# Sheet1_MCU.net
KiCad netlist of a schematic drawn in Altium Designer
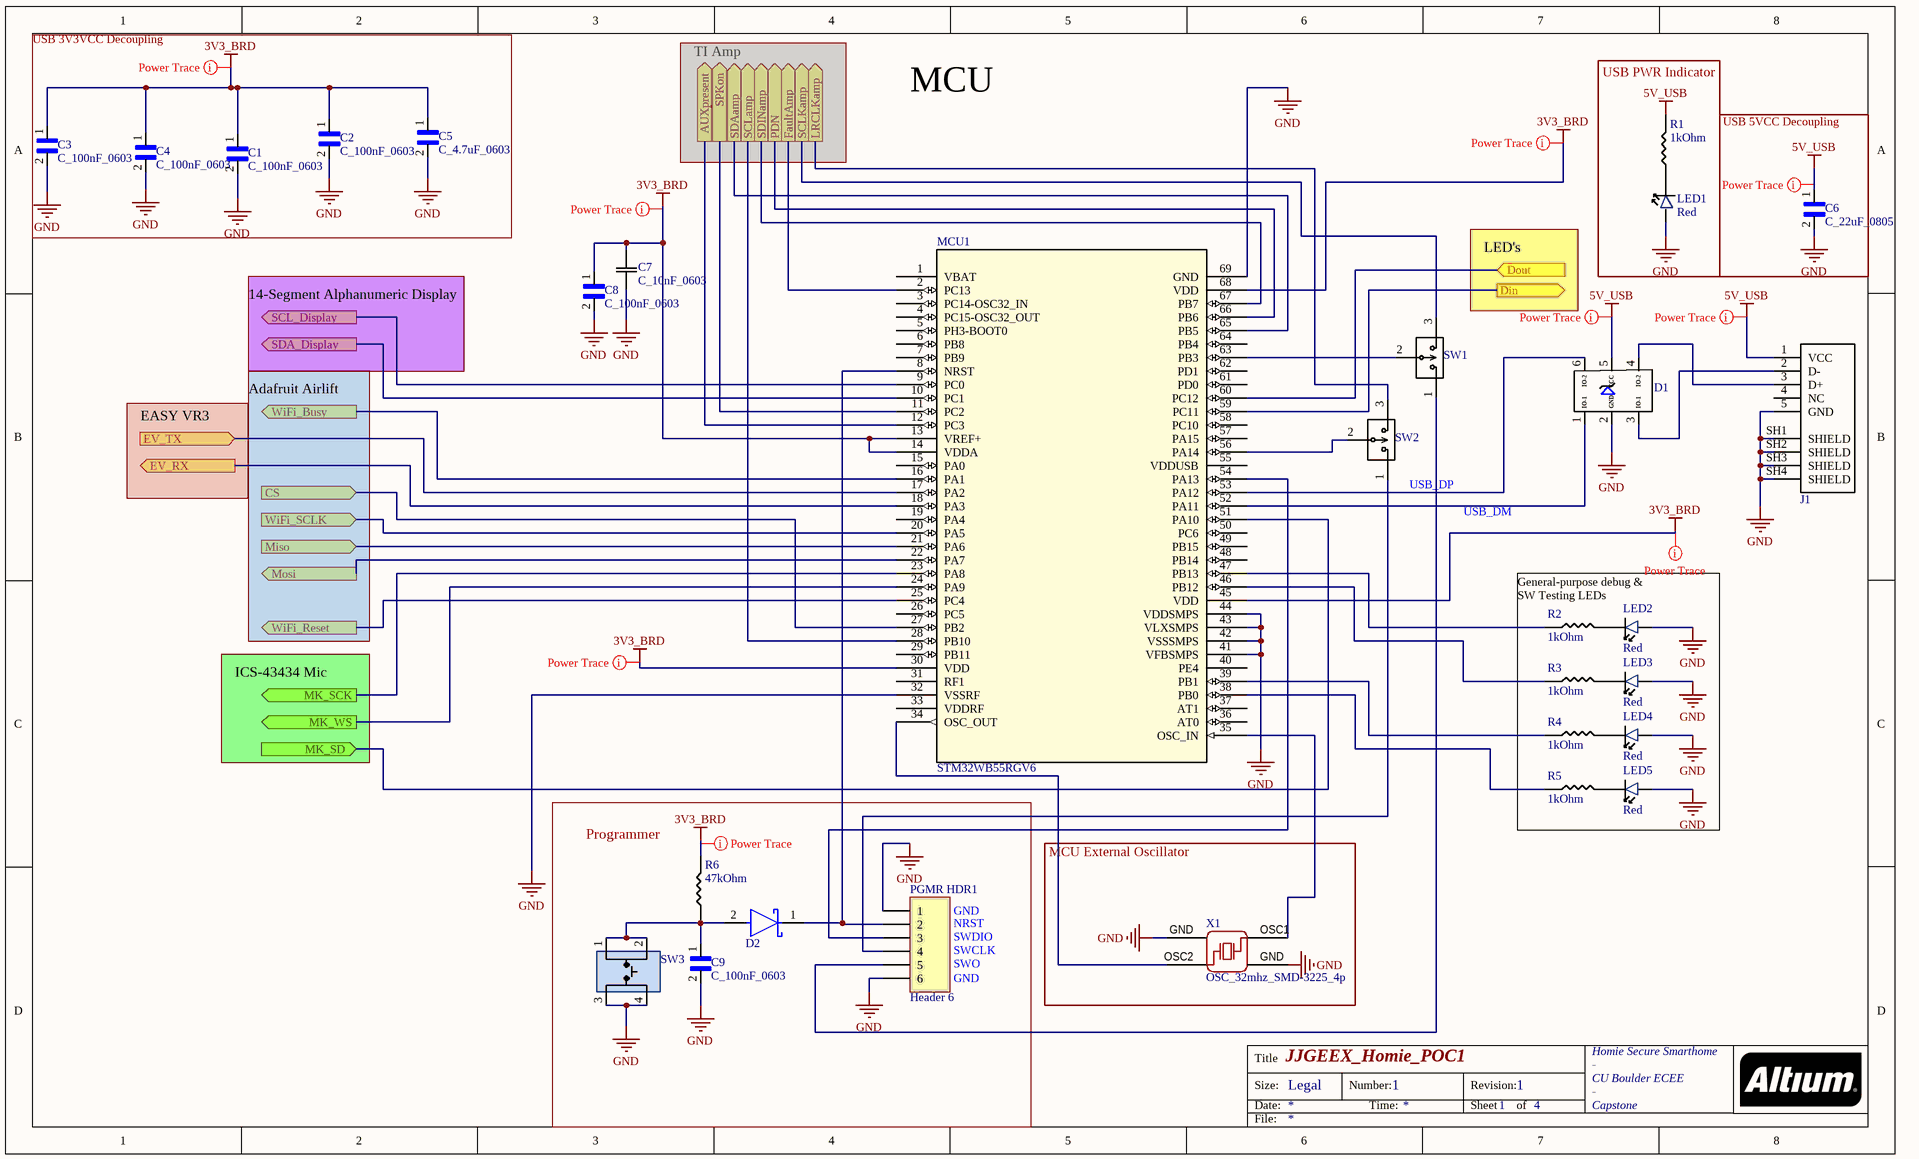
[diagram p0: Sheet1_MCU.SchDoc]

(export (version "E")
  (design (tool "Eeschema 10.0.6"))
  (components
    (comp (ref "C1")
      (value "C_100nF_0603")
      (footprint "CAPC1608X90")
      (description "0.1礔/100nF  卤10% 50V Ceramic Capacitor X7R 0603 _1608 Metric_")
      (fields (field (name "DIGI-KEY_PART_NUMBER") "311-1344-1-ND") (field (name "MP") "CC0603KRX7R9BB104"))
      (libsource (lib "Homie_IntegratedLibraryV2") (part "C_100nF_0603"))
    )
    (comp (ref "C2")
      (value "C_100nF_0603")
      (footprint "CAPC1608X90")
      (description "0.1礔/100nF  卤10% 50V Ceramic Capacitor X7R 0603 _1608 Metric_")
      (fields (field (name "DIGI-KEY_PART_NUMBER") "311-1344-1-ND") (field (name "MP") "CC0603KRX7R9BB104"))
      (libsource (lib "Homie_IntegratedLibraryV2") (part "C_100nF_0603"))
    )
    (comp (ref "C3")
      (value "C_100nF_0603")
      (footprint "CAPC1608X90")
      (description "0.1礔/100nF  卤10% 50V Ceramic Capacitor X7R 0603 _1608 Metric_")
      (fields (field (name "DIGI-KEY_PART_NUMBER") "311-1344-1-ND") (field (name "MP") "CC0603KRX7R9BB104"))
      (libsource (lib "Homie_IntegratedLibraryV2") (part "C_100nF_0603"))
    )
    (comp (ref "C4")
      (value "C_100nF_0603")
      (footprint "CAPC1608X90")
      (description "0.1礔/100nF  卤10% 50V Ceramic Capacitor X7R 0603 _1608 Metric_")
      (fields (field (name "DIGI-KEY_PART_NUMBER") "311-1344-1-ND") (field (name "MP") "CC0603KRX7R9BB104"))
      (libsource (lib "Homie_IntegratedLibraryV2") (part "C_100nF_0603"))
    )
    (comp (ref "C5")
      (value "C_4.7uF_0603")
      (footprint "CAPC1608X90N")
      (description "4.7µF ±10% 16V Ceramic Capacitor X5R 0603 (1608 Metric)")
      (fields (field (name "MF") "Samsung Electro-Mechanics") (field (name "MP") "CL10A475KO8NNNC"))
      (libsource (lib "Homie_IntegratedLibraryV2") (part "C_4.7uF_0603"))
    )
    (comp (ref "C6")
      (value "C_22uF_0805")
      (footprint "CAPC2012X140N")
      (description "22µF 0805 ±20% 25V Ceramic Capacitor X5R 0805 (2012 Metric)")
      (fields (field (name "MF") "Samsung") (field (name "DIGI-KEY_PART_NUMBER") "1276-2908-1-ND"))
      (libsource (lib "Homie_IntegratedLibraryV2") (part "C_22uF_0805"))
    )
    (comp (ref "C7")
      (value "C_10nF_0603")
      (footprint "CAP_0603_S_WAL")
      (description "10nf 0603 cap")
      (fields
        (field (name "MANUFACTURER_PART_NUMBER") "0603B103J100CT")
        (field (name "COPYRIGHT") "Copyright (C) 2018 Accelerated Designs. All rights reserved")
      )
      (libsource (lib "Homie_IntegratedLibraryV2") (part "C_10nF_0603"))
    )
    (comp (ref "C8")
      (value "C_100nF_0603")
      (footprint "CAPC1608X90")
      (description "0.1礔/100nF  卤10% 50V Ceramic Capacitor X7R 0603 _1608 Metric_")
      (fields (field (name "DIGI-KEY_PART_NUMBER") "311-1344-1-ND") (field (name "MP") "CC0603KRX7R9BB104"))
      (libsource (lib "Homie_IntegratedLibraryV2") (part "C_100nF_0603"))
    )
    (comp (ref "C9")
      (value "C_100nF_0603")
      (footprint "CAPC1608X90")
      (description "0.1礔/100nF  卤10% 50V Ceramic Capacitor X7R 0603 _1608 Metric_")
      (fields (field (name "DIGI-KEY_PART_NUMBER") "311-1344-1-ND") (field (name "MP") "CC0603KRX7R9BB104"))
      (libsource (lib "Homie_IntegratedLibraryV2") (part "C_100nF_0603"))
    )
    (comp (ref "D1")
      (value "IP4234CZ6,125")
      (footprint "TVS")
      (description "Clamp Ipp Tvs Diode Surface Mount 6-TSOP")
      (fields (field (name "DIGIKEY PART") "1727-4717-1-ND") (field (name "LCSC PART#") "C455086"))
      (libsource (lib "ECEN5730Lib_2020_09_AR") (part "D_TVS_Diode"))
    )
    (comp (ref "D2")
      (value "BAT54KFILM")
      (footprint "STMicroelectronics_SOD-523_MFG")
      (description "BAT54 Diode")
      (fields (field (name "MANUFACTURER") "STMicroelectronics"))
      (libsource (lib "Homie_IntegratedLibraryV2") (part "BAT54KFILM"))
    )
    (comp (ref "J1")
      (value "XM7D-0512")
      (footprint "USB_2")
      (description "USB - mini B USB 2.0 Receptacle Connector 5 Position Through Hole, Right Angle")
      (fields (field (name "DIGIKEY PART") "OR1205-ND"))
      (libsource (lib "ECEN5730Lib_2020_09_AR") (part "J_USB_2_B_Mini"))
    )
    (comp (ref "LED1")
      (value "Red")
      (footprint "LED0603-R-RD")
      (description "LIGHT EMITTING DIODES (LED) RED 520~625NM 90~100MCD@20MA TOP VIEW 0603 ROHS")
      (fields (field (name "MFR") "Hubei KENTO Elec") (field (name "Comment") "KT-0603R"))
      (libsource (lib "Homie_IntegratedLibraryV2") (part "LED_RED_0603"))
    )
    (comp (ref "LED2")
      (value "Red")
      (footprint "LED0603-R-RD")
      (description "LIGHT EMITTING DIODES (LED) RED 520~625NM 90~100MCD@20MA TOP VIEW 0603 ROHS")
      (fields (field (name "MFR") "Hubei KENTO Elec") (field (name "Comment") "KT-0603R"))
      (libsource (lib "Homie_IntegratedLibraryV2") (part "LED_RED_0603"))
    )
    (comp (ref "LED3")
      (value "Red")
      (footprint "LED0603-R-RD")
      (description "LIGHT EMITTING DIODES (LED) RED 520~625NM 90~100MCD@20MA TOP VIEW 0603 ROHS")
      (fields (field (name "MFR") "Hubei KENTO Elec") (field (name "Comment") "KT-0603R"))
      (libsource (lib "Homie_IntegratedLibraryV2") (part "LED_RED_0603"))
    )
    (comp (ref "LED4")
      (value "Red")
      (footprint "LED0603-R-RD")
      (description "LIGHT EMITTING DIODES (LED) RED 520~625NM 90~100MCD@20MA TOP VIEW 0603 ROHS")
      (fields (field (name "MFR") "Hubei KENTO Elec") (field (name "Comment") "KT-0603R"))
      (libsource (lib "Homie_IntegratedLibraryV2") (part "LED_RED_0603"))
    )
    (comp (ref "LED5")
      (value "Red")
      (footprint "LED0603-R-RD")
      (description "LIGHT EMITTING DIODES (LED) RED 520~625NM 90~100MCD@20MA TOP VIEW 0603 ROHS")
      (fields (field (name "MFR") "Hubei KENTO Elec") (field (name "Comment") "KT-0603R"))
      (libsource (lib "Homie_IntegratedLibraryV2") (part "LED_RED_0603"))
    )
    (comp (ref "MCU1")
      (value "STM32WB55RGV6")
      (footprint "VFQFPN68_8X8_STM")
      (description "STM32 Microcontroller")
      (fields (field (name "COPYRIGHT") "Copyright (C) 2018 Accelerated Designs. All rights reserved"))
      (libsource (lib "Homie_IntegratedLibraryV2") (part "STM32WB55RGV6"))
    )
    (comp (ref "PGMR HDR1")
      (value "Header 6")
      (footprint "HDR1X6")
      (description "Header, 6-Pin")
      (fields (field (name "PUBLISHER") "Altium Limited"))
      (libsource (lib "Miscellaneous Connectors") (part "Header 6"))
    )
    (comp (ref "R1")
      (value "1kOhm")
      (footprint "R0603")
      (description "1kOhm +-1%  0603")
      (fields (field (name "MFR") "Uniroyal") (field (name "Comment") "1 kOhm"))
      (libsource (lib "Homie_IntegratedLibraryV2") (part "R_1kOhm_0603"))
    )
    (comp (ref "R2")
      (value "1kOhm")
      (footprint "R0603")
      (description "1kOhm +-1%  0603")
      (fields (field (name "MFR") "Uniroyal") (field (name "Comment") "1 kOhm"))
      (libsource (lib "Homie_IntegratedLibraryV2") (part "R_1kOhm_0603"))
    )
    (comp (ref "R3")
      (value "1kOhm")
      (footprint "R0603")
      (description "1kOhm +-1%  0603")
      (fields (field (name "MFR") "Uniroyal") (field (name "Comment") "1 kOhm"))
      (libsource (lib "Homie_IntegratedLibraryV2") (part "R_1kOhm_0603"))
    )
    (comp (ref "R4")
      (value "1kOhm")
      (footprint "R0603")
      (description "1kOhm +-1%  0603")
      (fields (field (name "MFR") "Uniroyal") (field (name "Comment") "1 kOhm"))
      (libsource (lib "Homie_IntegratedLibraryV2") (part "R_1kOhm_0603"))
    )
    (comp (ref "R5")
      (value "1kOhm")
      (footprint "R0603")
      (description "1kOhm +-1%  0603")
      (fields (field (name "MFR") "Uniroyal") (field (name "Comment") "1 kOhm"))
      (libsource (lib "Homie_IntegratedLibraryV2") (part "R_1kOhm_0603"))
    )
    (comp (ref "R6")
      (value "47kOhm")
      (footprint "R0603")
      (description "47kOhm +-1%")
      (fields (field (name "MFR") "Uniroyal") (field (name "Comment") "47 kOhm"))
      (libsource (lib "Homie_IntegratedLibraryV2") (part "R_47kOhm_0603"))
    )
    (comp (ref "SW1")
      (value "PREC003SAAN-RC")
      (footprint "3_PIN_100mil")
      (description "Connector Header Through Hole 3 position 0.100\" (2.54mm)")
      (fields (field (name "DIGIKEY PART") "S1012EC-03-ND"))
      (libsource (lib "ECEN5730Lib_2020_09_AR") (part "SW_3Pin_100mil_Switch"))
    )
    (comp (ref "SW2")
      (value "PREC003SAAN-RC")
      (footprint "3_PIN_100mil")
      (description "Connector Header Through Hole 3 position 0.100\" (2.54mm)")
      (fields (field (name "DIGIKEY PART") "S1012EC-03-ND"))
      (libsource (lib "ECEN5730Lib_2020_09_AR") (part "SW_3Pin_100mil_Switch"))
    )
    (comp (ref "SW3")
      (value "TL3305AF160QG")
      (footprint "Switch_JLC")
      (description "Tactile Switch SPST-NO Top Actuated Surface Mount")
      (fields (field (name "DIGIKEY PART") "EG5350CT-ND") (field (name "MFR PART #") "UK-B0228-G5-160-JZ"))
      (libsource (lib "ECEN5730Lib_2020_09_AR") (part "SW_Push_Button_JLC"))
    )
    (comp (ref "X1")
      (value "OSC_32mhz_SMD-3225_4p")
      (footprint "OSC-SMD_4P-L3.2-W2.5-BL")
      (description "SMD CRYSTAL RESONATORS 32MHZ ±10PPM SMD-3225_4P ROHS")
      (fields (field (name "MFR") "Seiko Epson"))
      (libsource (lib "Homie_IntegratedLibraryV2") (part "OSC_32mhz_SMD-3225_4p"))
    )
  )
  (nets
    (net (code "1") (name "/AUXpresent") (class "Default")
      (node (ref "MCU1") (pin "12") (pinfunction "PC3_12") (pintype "bidirectional"))
    )
    (net (code "2") (name "/CS") (class "Default")
      (node (ref "MCU1") (pin "27") (pinfunction "PB2_27") (pintype "bidirectional"))
    )
    (net (code "3") (name "/Din") (class "Default")
      (node (ref "MCU1") (pin "59") (pinfunction "PC11_59") (pintype "bidirectional"))
    )
    (net (code "4") (name "/Dout") (class "Default")
      (node (ref "MCU1") (pin "60") (pinfunction "PC12_60") (pintype "bidirectional"))
    )
    (net (code "5") (name "/EV_RX") (class "Default")
      (node (ref "MCU1") (pin "18") (pinfunction "PA3_18") (pintype "bidirectional"))
    )
    (net (code "6") (name "/EV_TX") (class "Default")
      (node (ref "MCU1") (pin "17") (pinfunction "PA2_17") (pintype "bidirectional"))
    )
    (net (code "7") (name "/FaultAmp") (class "Default")
      (node (ref "MCU1") (pin "2") (pinfunction "PC13_2") (pintype "bidirectional"))
    )
    (net (code "8") (name "/LRCLKamp") (class "Default")
      (node (ref "SW2") (pin "3") (pinfunction "3_3") (pintype "passive"))
    )
    (net (code "9") (name "/MK_SCK") (class "Default")
      (node (ref "MCU1") (pin "23") (pinfunction "PA8_23") (pintype "bidirectional"))
    )
    (net (code "10") (name "/MK_SD") (class "Default")
      (node (ref "MCU1") (pin "51") (pinfunction "PA10_51") (pintype "bidirectional"))
    )
    (net (code "11") (name "/MK_WS") (class "Default")
      (node (ref "MCU1") (pin "24") (pinfunction "PA9_24") (pintype "bidirectional"))
    )
    (net (code "12") (name "/Miso") (class "Default")
      (node (ref "MCU1") (pin "21") (pinfunction "PA6_21") (pintype "bidirectional"))
    )
    (net (code "13") (name "/Mosi") (class "Default")
      (node (ref "MCU1") (pin "22") (pinfunction "PA7_22") (pintype "bidirectional"))
    )
    (net (code "14") (name "/PDN") (class "Default")
      (node (ref "MCU1") (pin "66") (pinfunction "PB6_66") (pintype "bidirectional"))
    )
    (net (code "15") (name "/SCLKamp") (class "Default")
      (node (ref "SW1") (pin "3") (pinfunction "3_3") (pintype "passive"))
    )
    (net (code "16") (name "/SCL_Display") (class "Default")
      (node (ref "MCU1") (pin "9") (pinfunction "PC0_9") (pintype "bidirectional"))
    )
    (net (code "17") (name "/SCLamp") (class "Default")
      (node (ref "MCU1") (pin "28") (pinfunction "PB10_28") (pintype "bidirectional"))
    )
    (net (code "18") (name "/SDA_Display") (class "Default")
      (node (ref "MCU1") (pin "10") (pinfunction "PC1_10") (pintype "bidirectional"))
    )
    (net (code "19") (name "/SDAamp") (class "Default")
      (node (ref "MCU1") (pin "65") (pinfunction "PB5_65") (pintype "bidirectional"))
    )
    (net (code "20") (name "/SDINamp") (class "Default")
      (node (ref "MCU1") (pin "67") (pinfunction "PB7_67") (pintype "bidirectional"))
    )
    (net (code "21") (name "/SPKon") (class "Default")
      (node (ref "MCU1") (pin "11") (pinfunction "PC2_11") (pintype "bidirectional"))
    )
    (net (code "22") (name "/WiFi_Busy") (class "Default")
      (node (ref "MCU1") (pin "16") (pinfunction "PA1_16") (pintype "bidirectional"))
    )
    (net (code "23") (name "/WiFi_Reset") (class "Default")
      (node (ref "MCU1") (pin "25") (pinfunction "PC4_25") (pintype "bidirectional"))
    )
    (net (code "24") (name "/WiFi_SCLK") (class "Default")
      (node (ref "MCU1") (pin "20") (pinfunction "PA5_20") (pintype "bidirectional"))
    )
    (net (code "25") (name "3V3_BRD") (class "Default")
      (node (ref "C1") (pin "1") (pinfunction "1_1") (pintype "passive"))
      (node (ref "C2") (pin "1") (pinfunction "1_1") (pintype "passive"))
      (node (ref "C3") (pin "1") (pinfunction "1_1") (pintype "passive"))
      (node (ref "C4") (pin "1") (pinfunction "1_1") (pintype "passive"))
      (node (ref "C5") (pin "1") (pinfunction "1_1") (pintype "passive"))
      (node (ref "C7") (pin "2") (pinfunction "2_2") (pintype "passive"))
      (node (ref "C8") (pin "1") (pinfunction "1_1") (pintype "passive"))
      (node (ref "MCU1") (pin "13") (pinfunction "VREF+_13") (pintype "power_in"))
      (node (ref "MCU1") (pin "14") (pinfunction "VDDA_14") (pintype "power_in"))
      (node (ref "MCU1") (pin "30") (pinfunction "VDD_30") (pintype "power_in"))
      (node (ref "MCU1") (pin "45") (pinfunction "VDD_45") (pintype "power_in"))
      (node (ref "MCU1") (pin "68") (pinfunction "VDD_68") (pintype "power_in"))
      (node (ref "R6") (pin "2") (pinfunction "2_2") (pintype "passive"))
    )
    (net (code "26") (name "5V_USB") (class "Default")
      (node (ref "C6") (pin "1") (pinfunction "1_1") (pintype "passive"))
      (node (ref "D1") (pin "5") (pinfunction "VCC_5") (pintype "passive"))
      (node (ref "J1") (pin "1") (pinfunction "VCC_1") (pintype "passive"))
      (node (ref "R1") (pin "2") (pinfunction "2_2") (pintype "passive"))
    )
    (net (code "27") (name "GND") (class "Default")
      (node (ref "C1") (pin "2") (pinfunction "2_2") (pintype "passive"))
      (node (ref "C2") (pin "2") (pinfunction "2_2") (pintype "passive"))
      (node (ref "C3") (pin "2") (pinfunction "2_2") (pintype "passive"))
      (node (ref "C4") (pin "2") (pinfunction "2_2") (pintype "passive"))
      (node (ref "C5") (pin "2") (pinfunction "2_2") (pintype "passive"))
      (node (ref "C6") (pin "2") (pinfunction "2_2") (pintype "passive"))
      (node (ref "C7") (pin "1") (pinfunction "1_1") (pintype "passive"))
      (node (ref "C8") (pin "2") (pinfunction "2_2") (pintype "passive"))
      (node (ref "C9") (pin "2") (pinfunction "2_2") (pintype "passive"))
      (node (ref "D1") (pin "2") (pinfunction "GND_2") (pintype "passive"))
      (node (ref "J1") (pin "5") (pinfunction "GND_5") (pintype "passive"))
      (node (ref "J1") (pin "SH1") (pinfunction "SHIELD_SH1") (pintype "passive"))
      (node (ref "J1") (pin "SH2") (pinfunction "SHIELD_SH2") (pintype "passive"))
      (node (ref "J1") (pin "SH3") (pinfunction "SHIELD_SH3") (pintype "passive"))
      (node (ref "J1") (pin "SH4") (pinfunction "SHIELD_SH4") (pintype "passive"))
      (node (ref "LED1") (pin "2") (pinfunction "2_2") (pintype "passive"))
      (node (ref "LED2") (pin "2") (pinfunction "2_2") (pintype "passive"))
      (node (ref "LED3") (pin "2") (pinfunction "2_2") (pintype "passive"))
      (node (ref "LED4") (pin "2") (pinfunction "2_2") (pintype "passive"))
      (node (ref "LED5") (pin "2") (pinfunction "2_2") (pintype "passive"))
      (node (ref "MCU1") (pin "32") (pinfunction "VSSRF_32") (pintype "passive"))
      (node (ref "MCU1") (pin "41") (pinfunction "VFBSMPS_41") (pintype "passive"))
      (node (ref "MCU1") (pin "42") (pinfunction "VSSSMPS_42") (pintype "passive"))
      (node (ref "MCU1") (pin "43") (pinfunction "VLXSMPS_43") (pintype "passive"))
      (node (ref "MCU1") (pin "44") (pinfunction "VDDSMPS_44") (pintype "power_in"))
      (node (ref "MCU1") (pin "69") (pinfunction "GND_69") (pintype "passive"))
      (node (ref "PGMR HDR1") (pin "1") (pinfunction "1_1") (pintype "passive"))
      (node (ref "PGMR HDR1") (pin "6") (pinfunction "6_6") (pintype "passive"))
      (node (ref "SW3") (pin "3") (pinfunction "3_3") (pintype "passive"))
      (node (ref "SW3") (pin "4") (pinfunction "4_4") (pintype "passive"))
      (node (ref "X1") (pin "GND") (pinfunction "3_GND") (pintype "passive"))
    )
    (net (code "28") (name "Net-(D2-A)") (class "Default")
      (node (ref "C9") (pin "1") (pinfunction "1_1") (pintype "passive"))
      (node (ref "D2") (pin "2") (pinfunction "A_2") (pintype "passive"))
      (node (ref "R6") (pin "1") (pinfunction "1_1") (pintype "passive"))
      (node (ref "SW3") (pin "1") (pinfunction "1_1") (pintype "passive"))
      (node (ref "SW3") (pin "2") (pinfunction "2_2") (pintype "passive"))
    )
    (net (code "29") (name "Net-(D2-C)") (class "Default")
      (node (ref "D2") (pin "1") (pinfunction "C_1") (pintype "passive"))
      (node (ref "MCU1") (pin "8") (pinfunction "NRST_8") (pintype "bidirectional"))
      (node (ref "PGMR HDR1") (pin "2") (pinfunction "2_2") (pintype "passive"))
    )
    (net (code "30") (name "Net-(J1-D+)") (class "Default")
      (node (ref "D1") (pin "4") (pinfunction "IO-2_4") (pintype "passive"))
      (node (ref "J1") (pin "3") (pinfunction "D+_3") (pintype "passive"))
    )
    (net (code "31") (name "Net-(J1-D-)") (class "Default")
      (node (ref "D1") (pin "3") (pinfunction "IO-1_3") (pintype "passive"))
      (node (ref "J1") (pin "2") (pinfunction "D-_2") (pintype "passive"))
    )
    (net (code "32") (name "Net-(LED1-Pad1)") (class "Default")
      (node (ref "LED1") (pin "1") (pinfunction "1_1") (pintype "passive"))
      (node (ref "R1") (pin "1") (pinfunction "1_1") (pintype "passive"))
    )
    (net (code "33") (name "Net-(LED2-Pad1)") (class "Default")
      (node (ref "LED2") (pin "1") (pinfunction "1_1") (pintype "passive"))
      (node (ref "R2") (pin "2") (pinfunction "2_2") (pintype "passive"))
    )
    (net (code "34") (name "Net-(LED3-Pad1)") (class "Default")
      (node (ref "LED3") (pin "1") (pinfunction "1_1") (pintype "passive"))
      (node (ref "R3") (pin "2") (pinfunction "2_2") (pintype "passive"))
    )
    (net (code "35") (name "Net-(LED4-Pad1)") (class "Default")
      (node (ref "LED4") (pin "1") (pinfunction "1_1") (pintype "passive"))
      (node (ref "R4") (pin "2") (pinfunction "2_2") (pintype "passive"))
    )
    (net (code "36") (name "Net-(LED5-Pad1)") (class "Default")
      (node (ref "LED5") (pin "1") (pinfunction "1_1") (pintype "passive"))
      (node (ref "R5") (pin "2") (pinfunction "2_2") (pintype "passive"))
    )
    (net (code "37") (name "Net-(MCU1-OSC_IN)") (class "Default")
      (node (ref "MCU1") (pin "35") (pinfunction "OSC_IN_35") (pintype "input"))
      (node (ref "X1") (pin "OSC1") (pinfunction "1_OSC1") (pintype "passive"))
    )
    (net (code "38") (name "Net-(MCU1-OSC_OUT)") (class "Default")
      (node (ref "MCU1") (pin "34") (pinfunction "OSC_OUT_34") (pintype "output"))
      (node (ref "X1") (pin "OSC2") (pinfunction "2_OSC2") (pintype "passive"))
    )
    (net (code "39") (name "Net-(MCU1-PA11)") (class "Default")
      (node (ref "D1") (pin "1") (pinfunction "IO-1_1") (pintype "passive"))
      (node (ref "MCU1") (pin "52") (pinfunction "PA11_52") (pintype "bidirectional"))
    )
    (net (code "40") (name "Net-(MCU1-PA12)") (class "Default")
      (node (ref "D1") (pin "6") (pinfunction "IO-2_6") (pintype "passive"))
      (node (ref "MCU1") (pin "53") (pinfunction "PA12_53") (pintype "bidirectional"))
    )
    (net (code "41") (name "Net-(MCU1-PA13)") (class "Default")
      (node (ref "MCU1") (pin "54") (pinfunction "PA13_54") (pintype "bidirectional"))
      (node (ref "PGMR HDR1") (pin "3") (pinfunction "3_3") (pintype "passive"))
    )
    (net (code "42") (name "Net-(MCU1-PA14)") (class "Default")
      (node (ref "MCU1") (pin "56") (pinfunction "PA14_56") (pintype "bidirectional"))
      (node (ref "SW2") (pin "2") (pinfunction "2_2") (pintype "passive"))
    )
    (net (code "43") (name "Net-(MCU1-PB0)") (class "Default")
      (node (ref "MCU1") (pin "38") (pinfunction "PB0_38") (pintype "bidirectional"))
      (node (ref "R5") (pin "1") (pinfunction "1_1") (pintype "passive"))
    )
    (net (code "44") (name "Net-(MCU1-PB1)") (class "Default")
      (node (ref "MCU1") (pin "39") (pinfunction "PB1_39") (pintype "bidirectional"))
      (node (ref "R4") (pin "1") (pinfunction "1_1") (pintype "passive"))
    )
    (net (code "45") (name "Net-(MCU1-PB3)") (class "Default")
      (node (ref "MCU1") (pin "63") (pinfunction "PB3_63") (pintype "bidirectional"))
      (node (ref "SW1") (pin "2") (pinfunction "2_2") (pintype "passive"))
    )
    (net (code "46") (name "Net-(MCU1-PB12)") (class "Default")
      (node (ref "MCU1") (pin "46") (pinfunction "PB12_46") (pintype "bidirectional"))
      (node (ref "R3") (pin "1") (pinfunction "1_1") (pintype "passive"))
    )
    (net (code "47") (name "Net-(MCU1-PB13)") (class "Default")
      (node (ref "MCU1") (pin "47") (pinfunction "PB13_47") (pintype "bidirectional"))
      (node (ref "R2") (pin "1") (pinfunction "1_1") (pintype "passive"))
    )
    (net (code "48") (name "Net-(PGMR HDR1-Pad4)") (class "Default")
      (node (ref "PGMR HDR1") (pin "4") (pinfunction "4_4") (pintype "passive"))
      (node (ref "SW2") (pin "1") (pinfunction "1_1") (pintype "passive"))
    )
    (net (code "49") (name "Net-(PGMR HDR1-Pad5)") (class "Default")
      (node (ref "PGMR HDR1") (pin "5") (pinfunction "5_5") (pintype "passive"))
      (node (ref "SW1") (pin "1") (pinfunction "1_1") (pintype "passive"))
    )
    (net (code "50") (name "unconnected-(J1-NC-Pad4)") (class "Default")
      (node (ref "J1") (pin "4") (pinfunction "NC_4") (pintype "passive"))
    )
    (net (code "51") (name "unconnected-(MCU1-AT0-Pad36)") (class "Default")
      (node (ref "MCU1") (pin "36") (pinfunction "AT0_36") (pintype "bidirectional"))
    )
    (net (code "52") (name "unconnected-(MCU1-AT1-Pad37)") (class "Default")
      (node (ref "MCU1") (pin "37") (pinfunction "AT1_37") (pintype "bidirectional"))
    )
    (net (code "53") (name "unconnected-(MCU1-PA0-Pad15)") (class "Default")
      (node (ref "MCU1") (pin "15") (pinfunction "PA0_15") (pintype "bidirectional"))
    )
    (net (code "54") (name "unconnected-(MCU1-PA4-Pad19)") (class "Default")
      (node (ref "MCU1") (pin "19") (pinfunction "PA4_19") (pintype "bidirectional"))
    )
    (net (code "55") (name "unconnected-(MCU1-PA15-Pad57)") (class "Default")
      (node (ref "MCU1") (pin "57") (pinfunction "PA15_57") (pintype "bidirectional"))
    )
    (net (code "56") (name "unconnected-(MCU1-PB4-Pad64)") (class "Default")
      (node (ref "MCU1") (pin "64") (pinfunction "PB4_64") (pintype "bidirectional"))
    )
    (net (code "57") (name "unconnected-(MCU1-PB8-Pad6)") (class "Default")
      (node (ref "MCU1") (pin "6") (pinfunction "PB8_6") (pintype "bidirectional"))
    )
    (net (code "58") (name "unconnected-(MCU1-PB9-Pad7)") (class "Default")
      (node (ref "MCU1") (pin "7") (pinfunction "PB9_7") (pintype "bidirectional"))
    )
    (net (code "59") (name "unconnected-(MCU1-PB11-Pad29)") (class "Default")
      (node (ref "MCU1") (pin "29") (pinfunction "PB11_29") (pintype "bidirectional"))
    )
    (net (code "60") (name "unconnected-(MCU1-PB14-Pad48)") (class "Default")
      (node (ref "MCU1") (pin "48") (pinfunction "PB14_48") (pintype "bidirectional"))
    )
    (net (code "61") (name "unconnected-(MCU1-PB15-Pad49)") (class "Default")
      (node (ref "MCU1") (pin "49") (pinfunction "PB15_49") (pintype "bidirectional"))
    )
    (net (code "62") (name "unconnected-(MCU1-PC5-Pad26)") (class "Default")
      (node (ref "MCU1") (pin "26") (pinfunction "PC5_26") (pintype "bidirectional"))
    )
    (net (code "63") (name "unconnected-(MCU1-PC6-Pad50)") (class "Default")
      (node (ref "MCU1") (pin "50") (pinfunction "PC6_50") (pintype "bidirectional"))
    )
    (net (code "64") (name "unconnected-(MCU1-PC10-Pad58)") (class "Default")
      (node (ref "MCU1") (pin "58") (pinfunction "PC10_58") (pintype "bidirectional"))
    )
    (net (code "65") (name "unconnected-(MCU1-PC14-OSC32_IN-Pad3)") (class "Default")
      (node (ref "MCU1") (pin "3") (pinfunction "PC14-OSC32_IN_3") (pintype "bidirectional"))
    )
    (net (code "66") (name "unconnected-(MCU1-PC15-OSC32_OUT-Pad4)") (class "Default")
      (node (ref "MCU1") (pin "4") (pinfunction "PC15-OSC32_OUT_4") (pintype "bidirectional"))
    )
    (net (code "67") (name "unconnected-(MCU1-PD0-Pad61)") (class "Default")
      (node (ref "MCU1") (pin "61") (pinfunction "PD0_61") (pintype "bidirectional"))
    )
    (net (code "68") (name "unconnected-(MCU1-PD1-Pad62)") (class "Default")
      (node (ref "MCU1") (pin "62") (pinfunction "PD1_62") (pintype "bidirectional"))
    )
    (net (code "69") (name "unconnected-(MCU1-PE4-Pad40)") (class "Default")
      (node (ref "MCU1") (pin "40") (pinfunction "PE4_40") (pintype "passive"))
    )
    (net (code "70") (name "unconnected-(MCU1-PH3-BOOT0-Pad5)") (class "Default")
      (node (ref "MCU1") (pin "5") (pinfunction "PH3-BOOT0_5") (pintype "bidirectional"))
    )
    (net (code "71") (name "unconnected-(MCU1-RF1-Pad31)") (class "Default")
      (node (ref "MCU1") (pin "31") (pinfunction "RF1_31") (pintype "passive"))
    )
    (net (code "72") (name "unconnected-(MCU1-VBAT-Pad1)") (class "Default")
      (node (ref "MCU1") (pin "1") (pinfunction "VBAT_1") (pintype "power_in"))
    )
    (net (code "73") (name "unconnected-(MCU1-VDDRF-Pad33)") (class "Default")
      (node (ref "MCU1") (pin "33") (pinfunction "VDDRF_33") (pintype "power_in"))
    )
    (net (code "74") (name "unconnected-(MCU1-VDDUSB-Pad55)") (class "Default")
      (node (ref "MCU1") (pin "55") (pinfunction "VDDUSB_55") (pintype "power_in"))
    )
  )
)
